# design.net
KiCad netlist of a schematic drawn in Altium Designer
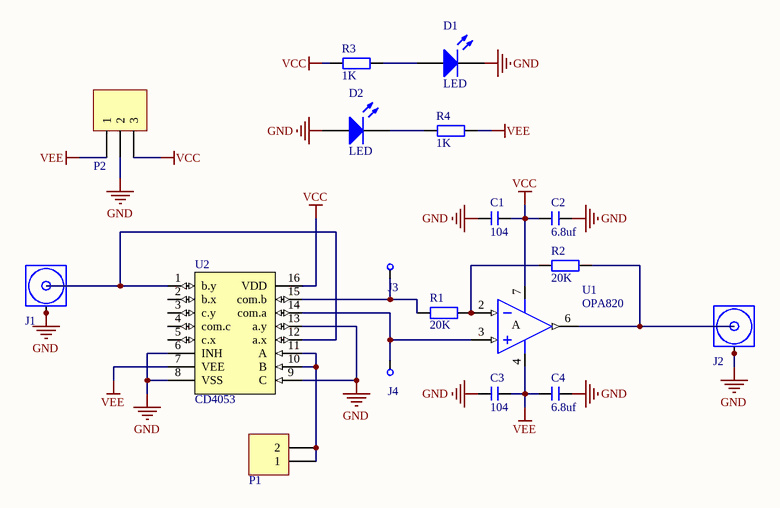
[diagram p0: 相敏检波器.SchDoc]

(export (version "E")
  (design (tool "Eeschema 10.0.6"))
  (components
    (comp (ref "C1")
      (value "104")
      (footprint "C 0805")
      (description "无极性贴片电容")
      (fields (field (name "版权归属") "源创客"))
      (libsource (lib "电阻-电容-电感") (part "C"))
    )
    (comp (ref "C2")
      (value "6.8uf")
      (footprint "C 0805")
      (description "无极性贴片电容")
      (fields (field (name "版权归属") "源创客"))
      (libsource (lib "电阻-电容-电感") (part "C"))
    )
    (comp (ref "C3")
      (value "104")
      (footprint "C 0805")
      (description "无极性贴片电容")
      (fields (field (name "版权归属") "源创客"))
      (libsource (lib "电阻-电容-电感") (part "C"))
    )
    (comp (ref "C4")
      (value "6.8uf")
      (footprint "C 0805")
      (description "无极性贴片电容")
      (fields (field (name "版权归属") "源创客"))
      (libsource (lib "电阻-电容-电感") (part "C"))
    )
    (comp (ref "D1")
      (value "LED")
      (footprint "LED_0805")
      (description "发光二极管")
      (fields (field (name "PUBLISHER") "Altium Limited"))
      (libsource (lib "LIB") (part "LED"))
    )
    (comp (ref "D2")
      (value "LED")
      (footprint "LED_0805")
      (description "发光二极管")
      (fields (field (name "PUBLISHER") "Altium Limited"))
      (libsource (lib "LIB") (part "LED"))
    )
    (comp (ref "J1") (value "COAX") (footprint "MCX5.08-5-H") (libsource (lib "LIB") (part "COAX")))
    (comp (ref "J2") (value "COAX") (footprint "MCX5.08-5-H") (libsource (lib "LIB") (part "COAX")))
    (comp (ref "J3")
      (value "CHECK")
      (footprint "CHECK-A")
      (description "测试点")
      (libsource (lib "LIB") (part "CHECK"))
    )
    (comp (ref "J4")
      (value "CHECK")
      (footprint "CHECK-A")
      (description "测试点")
      (libsource (lib "LIB") (part "CHECK"))
    )
    (comp (ref "P1")
      (value "Header 2")
      (footprint "HDR2X1_B2")
      (description "接插件")
      (fields (field (name "PUBLISHER") "Altium Limited"))
      (libsource (lib "LIB") (part "Header 2"))
    )
    (comp (ref "P2")
      (value "Header 3")
      (footprint "HDR3X1_B2")
      (description "接插件")
      (fields (field (name "PUBLISHER") "Altium Limited"))
      (libsource (lib "LIB") (part "Header 3"))
    )
    (comp (ref "R1")
      (value "20K")
      (footprint "R 0805")
      (description "贴片电阻")
      (fields (field (name "版权归属") "源创客"))
      (libsource (lib "电阻-电容-电感") (part "R"))
    )
    (comp (ref "R2")
      (value "20K")
      (footprint "R 0805")
      (description "贴片电阻")
      (fields (field (name "版权归属") "源创客"))
      (libsource (lib "电阻-电容-电感") (part "R"))
    )
    (comp (ref "R3")
      (value "1K")
      (footprint "R 0805")
      (description "贴片电阻")
      (fields (field (name "版权归属") "源创客"))
      (libsource (lib "电阻-电容-电感") (part "R"))
    )
    (comp (ref "R4")
      (value "1K")
      (footprint "R 0805")
      (description "贴片电阻")
      (fields (field (name "版权归属") "源创客"))
      (libsource (lib "电阻-电容-电感") (part "R"))
    )
    (comp (ref "U1")
      (value "OPA820")
      (footprint "SOIC8_N")
      (description "单位增益稳定低噪声电压反馈运算放大器")
      (libsource (lib "LIB") (part "OPA820"))
    )
    (comp (ref "U2")
      (value "CD4053")
      (footprint "NSO16_M")
      (description "CMOS Single 8-Channel Analog Multiplexer/Demultiplexer  With Logic-Level Conversion")
      (libsource (lib "LIB") (part "CD4053"))
    )
  )
  (nets
    (net (code "1") (name "GND") (class "Default")
      (node (ref "C1") (pin "1") (pinfunction "1_1") (pintype "passive"))
      (node (ref "C2") (pin "2") (pinfunction "2_2") (pintype "passive"))
      (node (ref "C3") (pin "1") (pinfunction "1_1") (pintype "passive"))
      (node (ref "C4") (pin "2") (pinfunction "2_2") (pintype "passive"))
      (node (ref "D1") (pin "2") (pinfunction "K_2") (pintype "passive"))
      (node (ref "D2") (pin "1") (pinfunction "A_1") (pintype "passive"))
      (node (ref "J1") (pin "2") (pinfunction "GND_2") (pintype "passive"))
      (node (ref "J1") (pin "3") (pinfunction "GND_3") (pintype "passive"))
      (node (ref "J1") (pin "4") (pinfunction "GND_4") (pintype "passive"))
      (node (ref "J1") (pin "5") (pinfunction "GND_5") (pintype "passive"))
      (node (ref "J2") (pin "2") (pinfunction "GND_2") (pintype "passive"))
      (node (ref "J2") (pin "3") (pinfunction "GND_3") (pintype "passive"))
      (node (ref "J2") (pin "4") (pinfunction "GND_4") (pintype "passive"))
      (node (ref "J2") (pin "5") (pinfunction "GND_5") (pintype "passive"))
      (node (ref "P2") (pin "2") (pinfunction "2_2") (pintype "passive"))
      (node (ref "U2") (pin "13") (pinfunction "a.y_13") (pintype "bidirectional"))
      (node (ref "U2") (pin "6") (pinfunction "INH_6") (pintype "passive"))
      (node (ref "U2") (pin "8") (pinfunction "VSS_8") (pintype "power_in"))
      (node (ref "U2") (pin "9") (pinfunction "C_9") (pintype "input"))
    )
    (net (code "2") (name "Net-(D1-A)") (class "Default")
      (node (ref "D1") (pin "1") (pinfunction "A_1") (pintype "passive"))
      (node (ref "R3") (pin "2") (pinfunction "2_2") (pintype "passive"))
    )
    (net (code "3") (name "Net-(D2-K)") (class "Default")
      (node (ref "D2") (pin "2") (pinfunction "K_2") (pintype "passive"))
      (node (ref "R4") (pin "1") (pinfunction "1_1") (pintype "passive"))
    )
    (net (code "4") (name "Net-(J1-Signal)") (class "Default")
      (node (ref "J1") (pin "1") (pinfunction "Signal_1") (pintype "passive"))
      (node (ref "U2") (pin "1") (pinfunction "b.y_1") (pintype "bidirectional"))
      (node (ref "U2") (pin "12") (pinfunction "a.x_12") (pintype "bidirectional"))
    )
    (net (code "5") (name "Net-(J2-Signal)") (class "Default")
      (node (ref "J2") (pin "1") (pinfunction "Signal_1") (pintype "passive"))
      (node (ref "R2") (pin "2") (pinfunction "2_2") (pintype "passive"))
      (node (ref "U1") (pin "6") (pinfunction "OUT_6") (pintype "output"))
    )
    (net (code "6") (name "Net-(U1-+IN)") (class "Default")
      (node (ref "J4") (pin "1") (pinfunction "1_1") (pintype "passive"))
      (node (ref "U1") (pin "3") (pinfunction "+IN_3") (pintype "input"))
      (node (ref "U2") (pin "14") (pinfunction "com.a_14") (pintype "bidirectional"))
    )
    (net (code "7") (name "Net-(U1--IN)") (class "Default")
      (node (ref "R1") (pin "2") (pinfunction "2_2") (pintype "passive"))
      (node (ref "R2") (pin "1") (pinfunction "1_1") (pintype "passive"))
      (node (ref "U1") (pin "2") (pinfunction "-IN_2") (pintype "input"))
    )
    (net (code "8") (name "Net-(U2-A)") (class "Default")
      (node (ref "P1") (pin "1") (pinfunction "1_1") (pintype "passive"))
      (node (ref "P1") (pin "2") (pinfunction "2_2") (pintype "passive"))
      (node (ref "U2") (pin "10") (pinfunction "B_10") (pintype "input"))
      (node (ref "U2") (pin "11") (pinfunction "A_11") (pintype "input"))
    )
    (net (code "9") (name "Net-(U2-com.b)") (class "Default")
      (node (ref "J3") (pin "1") (pinfunction "1_1") (pintype "passive"))
      (node (ref "R1") (pin "1") (pinfunction "1_1") (pintype "passive"))
      (node (ref "U2") (pin "15") (pinfunction "com.b_15") (pintype "bidirectional"))
    )
    (net (code "10") (name "VCC") (class "Default")
      (node (ref "C1") (pin "2") (pinfunction "2_2") (pintype "passive"))
      (node (ref "C2") (pin "1") (pinfunction "1_1") (pintype "passive"))
      (node (ref "P2") (pin "3") (pinfunction "3_3") (pintype "passive"))
      (node (ref "R3") (pin "1") (pinfunction "1_1") (pintype "passive"))
      (node (ref "U1") (pin "7") (pinfunction "V+_7") (pintype "power_in"))
      (node (ref "U2") (pin "16") (pinfunction "VDD_16") (pintype "power_in"))
    )
    (net (code "11") (name "VEE") (class "Default")
      (node (ref "C3") (pin "2") (pinfunction "2_2") (pintype "passive"))
      (node (ref "C4") (pin "1") (pinfunction "1_1") (pintype "passive"))
      (node (ref "P2") (pin "1") (pinfunction "1_1") (pintype "passive"))
      (node (ref "R4") (pin "2") (pinfunction "2_2") (pintype "passive"))
      (node (ref "U1") (pin "4") (pinfunction "V-_4") (pintype "power_in"))
      (node (ref "U2") (pin "7") (pinfunction "VEE_7") (pintype "power_in"))
    )
    (net (code "12") (name "unconnected-(U2-b.x-Pad2)") (class "Default")
      (node (ref "U2") (pin "2") (pinfunction "b.x_2") (pintype "bidirectional"))
    )
    (net (code "13") (name "unconnected-(U2-c.x-Pad5)") (class "Default")
      (node (ref "U2") (pin "5") (pinfunction "c.x_5") (pintype "bidirectional"))
    )
    (net (code "14") (name "unconnected-(U2-c.y-Pad3)") (class "Default")
      (node (ref "U2") (pin "3") (pinfunction "c.y_3") (pintype "bidirectional"))
    )
    (net (code "15") (name "unconnected-(U2-com.c-Pad4)") (class "Default")
      (node (ref "U2") (pin "4") (pinfunction "com.c_4") (pintype "bidirectional"))
    )
  )
)
